# ADC.net
KiCad netlist of a schematic drawn in EAGLE
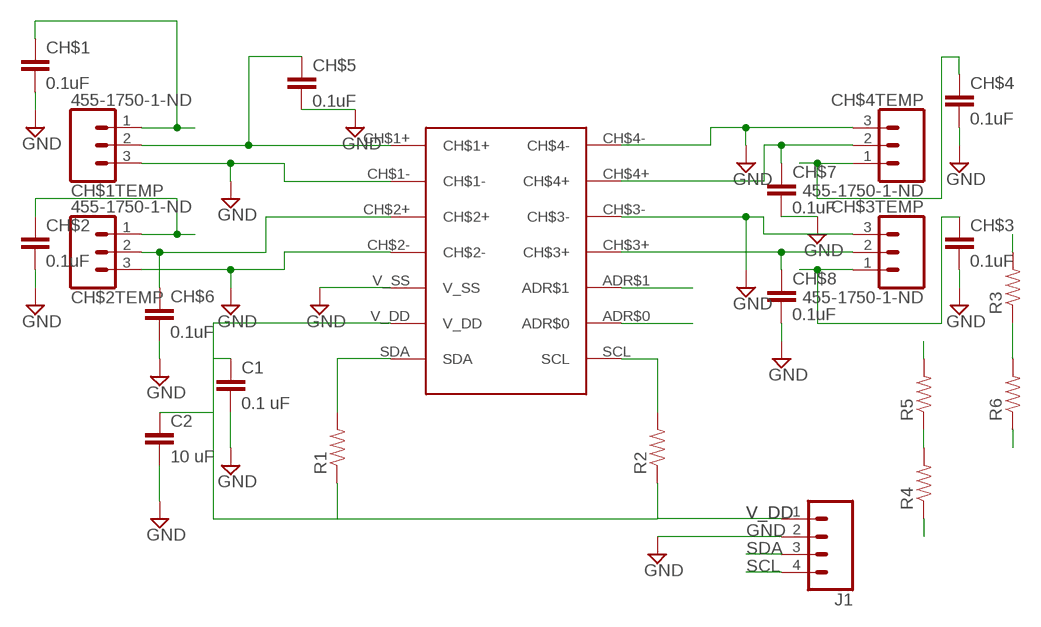
[diagram p0: schematic, sheet 1]

(export (version "E")
  (design (tool "Eeschema 10.0.6"))
  (components
    (comp (ref "C1")
      (value "0.1 uF")
      (footprint "eagle-import:0805")
      (libsource (lib "eagle-import") (part "CAPACITOR0805"))
    )
    (comp (ref "C2")
      (value "10 uF")
      (footprint "eagle-import:0805")
      (libsource (lib "eagle-import") (part "CAPACITOR0805"))
    )
    (comp (ref "CH$1")
      (value "0.1uF")
      (footprint "eagle-import:0805")
      (libsource (lib "eagle-import") (part "CAPACITOR0805"))
    )
    (comp (ref "CH$1TEMP")
      (value "455-1750-1-ND")
      (footprint "eagle-import:1X03")
      (libsource (lib "eagle-import") (part "CONN_03"))
    )
    (comp (ref "CH$2")
      (value "0.1uF")
      (footprint "eagle-import:0805")
      (libsource (lib "eagle-import") (part "CAPACITOR0805"))
    )
    (comp (ref "CH$2TEMP")
      (value "455-1750-1-ND")
      (footprint "eagle-import:1X03")
      (libsource (lib "eagle-import") (part "CONN_03"))
    )
    (comp (ref "CH$3")
      (value "0.1uF")
      (footprint "eagle-import:0805")
      (libsource (lib "eagle-import") (part "CAPACITOR0805"))
    )
    (comp (ref "CH$3TEMP")
      (value "455-1750-1-ND")
      (footprint "eagle-import:1X03")
      (libsource (lib "eagle-import") (part "CONN_03"))
    )
    (comp (ref "CH$4")
      (value "0.1uF")
      (footprint "eagle-import:0805")
      (libsource (lib "eagle-import") (part "CAPACITOR0805"))
    )
    (comp (ref "CH$4TEMP")
      (value "455-1750-1-ND")
      (footprint "eagle-import:1X03")
      (libsource (lib "eagle-import") (part "CONN_03"))
    )
    (comp (ref "CH$5")
      (value "0.1uF")
      (footprint "eagle-import:0805")
      (libsource (lib "eagle-import") (part "CAPACITOR0805"))
    )
    (comp (ref "CH$6")
      (value "0.1uF")
      (footprint "eagle-import:0805")
      (libsource (lib "eagle-import") (part "CAPACITOR0805"))
    )
    (comp (ref "CH$7")
      (value "0.1uF")
      (footprint "eagle-import:0805")
      (libsource (lib "eagle-import") (part "CAPACITOR0805"))
    )
    (comp (ref "CH$8")
      (value "0.1uF")
      (footprint "eagle-import:0805")
      (libsource (lib "eagle-import") (part "CAPACITOR0805"))
    )
    (comp (ref "J1")
      (value "CONN_04")
      (footprint "eagle-import:1X04")
      (libsource (lib "eagle-import") (part "CONN_04"))
    )
    (comp (ref "R1")
      (value "RESISTOR0805")
      (footprint "eagle-import:0805")
      (libsource (lib "eagle-import") (part "RESISTOR0805"))
    )
    (comp (ref "R2")
      (value "RESISTOR0805")
      (footprint "eagle-import:0805")
      (libsource (lib "eagle-import") (part "RESISTOR0805"))
    )
    (comp (ref "R3")
      (value "RESISTOR0805")
      (footprint "eagle-import:0805")
      (libsource (lib "eagle-import") (part "RESISTOR0805"))
    )
    (comp (ref "R4")
      (value "RESISTOR0805")
      (footprint "eagle-import:0805")
      (libsource (lib "eagle-import") (part "RESISTOR0805"))
    )
    (comp (ref "R5")
      (value "RESISTOR0805")
      (footprint "eagle-import:0805")
      (libsource (lib "eagle-import") (part "RESISTOR0805"))
    )
    (comp (ref "R6")
      (value "RESISTOR0805")
      (footprint "eagle-import:0805")
      (libsource (lib "eagle-import") (part "RESISTOR0805"))
    )
    (comp (ref "U$1")
      (value "MCP3428-E/SL")
      (footprint "eagle-import:MICROCHIP_MCP3428")
      (libsource (lib "eagle-import") (part "MCP3428-E/SL"))
    )
  )
  (nets
    (net (code "1") (name "/ADR0") (class "Default")
      (node (ref "R4") (pin "2") (pinfunction "2_2") (pintype "passive"))
      (node (ref "R5") (pin "1") (pinfunction "1_1") (pintype "passive"))
      (node (ref "U$1") (pin "ADR$0") (pinfunction "ADR$0_ADR$0") (pintype "bidirectional"))
    )
    (net (code "2") (name "/ADR1") (class "Default")
      (node (ref "R3") (pin "1") (pinfunction "1_1") (pintype "passive"))
      (node (ref "R6") (pin "2") (pinfunction "2_2") (pintype "passive"))
      (node (ref "U$1") (pin "ADR$1") (pinfunction "ADR$1_ADR$1") (pintype "bidirectional"))
    )
    (net (code "3") (name "/SCL") (class "Default")
      (node (ref "J1") (pin "4") (pinfunction "4_4") (pintype "passive"))
      (node (ref "R2") (pin "2") (pinfunction "2_2") (pintype "passive"))
      (node (ref "U$1") (pin "SCL") (pinfunction "SCL_SCL") (pintype "bidirectional"))
    )
    (net (code "4") (name "/SDA") (class "Default")
      (node (ref "J1") (pin "3") (pinfunction "3_3") (pintype "passive"))
      (node (ref "R1") (pin "2") (pinfunction "2_2") (pintype "passive"))
      (node (ref "U$1") (pin "SDA") (pinfunction "SDA_SDA") (pintype "bidirectional"))
    )
    (net (code "5") (name "/V_DD") (class "Default")
      (node (ref "C1") (pin "1") (pinfunction "1_1") (pintype "passive"))
      (node (ref "C2") (pin "1") (pinfunction "1_1") (pintype "passive"))
      (node (ref "CH$1") (pin "1") (pinfunction "1_1") (pintype "passive"))
      (node (ref "CH$1TEMP") (pin "1") (pinfunction "1_1") (pintype "passive"))
      (node (ref "CH$2") (pin "1") (pinfunction "1_1") (pintype "passive"))
      (node (ref "CH$2TEMP") (pin "1") (pinfunction "1_1") (pintype "passive"))
      (node (ref "CH$3") (pin "1") (pinfunction "1_1") (pintype "passive"))
      (node (ref "CH$3TEMP") (pin "1") (pinfunction "1_1") (pintype "passive"))
      (node (ref "CH$4") (pin "1") (pinfunction "1_1") (pintype "passive"))
      (node (ref "CH$4TEMP") (pin "1") (pinfunction "1_1") (pintype "passive"))
      (node (ref "J1") (pin "1") (pinfunction "1_1") (pintype "passive"))
      (node (ref "R1") (pin "1") (pinfunction "1_1") (pintype "passive"))
      (node (ref "R2") (pin "1") (pinfunction "1_1") (pintype "passive"))
      (node (ref "R3") (pin "2") (pinfunction "2_2") (pintype "passive"))
      (node (ref "R5") (pin "2") (pinfunction "2_2") (pintype "passive"))
      (node (ref "U$1") (pin "V_DD") (pinfunction "V_DD_V_DD") (pintype "bidirectional"))
    )
    (net (code "6") (name "GND") (class "Default")
      (node (ref "C1") (pin "2") (pinfunction "2_2") (pintype "passive"))
      (node (ref "C2") (pin "2") (pinfunction "2_2") (pintype "passive"))
      (node (ref "CH$1") (pin "2") (pinfunction "2_2") (pintype "passive"))
      (node (ref "CH$1TEMP") (pin "3") (pinfunction "3_3") (pintype "passive"))
      (node (ref "CH$2") (pin "2") (pinfunction "2_2") (pintype "passive"))
      (node (ref "CH$2TEMP") (pin "3") (pinfunction "3_3") (pintype "passive"))
      (node (ref "CH$3") (pin "2") (pinfunction "2_2") (pintype "passive"))
      (node (ref "CH$3TEMP") (pin "3") (pinfunction "3_3") (pintype "passive"))
      (node (ref "CH$4") (pin "2") (pinfunction "2_2") (pintype "passive"))
      (node (ref "CH$4TEMP") (pin "3") (pinfunction "3_3") (pintype "passive"))
      (node (ref "CH$5") (pin "2") (pinfunction "2_2") (pintype "passive"))
      (node (ref "CH$6") (pin "2") (pinfunction "2_2") (pintype "passive"))
      (node (ref "CH$7") (pin "2") (pinfunction "2_2") (pintype "passive"))
      (node (ref "CH$8") (pin "2") (pinfunction "2_2") (pintype "passive"))
      (node (ref "J1") (pin "2") (pinfunction "2_2") (pintype "passive"))
      (node (ref "R4") (pin "1") (pinfunction "1_1") (pintype "passive"))
      (node (ref "R6") (pin "1") (pinfunction "1_1") (pintype "passive"))
      (node (ref "U$1") (pin "CH$1-") (pinfunction "CH$1-_CH$1-") (pintype "bidirectional"))
      (node (ref "U$1") (pin "CH$2-") (pinfunction "CH$2-_CH$2-") (pintype "bidirectional"))
      (node (ref "U$1") (pin "CH$3-") (pinfunction "CH$3-_CH$3-") (pintype "bidirectional"))
      (node (ref "U$1") (pin "CH$4-") (pinfunction "CH$4-_CH$4-") (pintype "bidirectional"))
      (node (ref "U$1") (pin "V_SS") (pinfunction "V_SS_V_SS") (pintype "bidirectional"))
    )
    (net (code "7") (name "Net-(CH$1TEMP-Pad2)") (class "Default")
      (node (ref "CH$1TEMP") (pin "2") (pinfunction "2_2") (pintype "passive"))
      (node (ref "CH$5") (pin "1") (pinfunction "1_1") (pintype "passive"))
      (node (ref "U$1") (pin "CH$1+") (pinfunction "CH$1+_CH$1+") (pintype "bidirectional"))
    )
    (net (code "8") (name "Net-(CH$2TEMP-Pad2)") (class "Default")
      (node (ref "CH$2TEMP") (pin "2") (pinfunction "2_2") (pintype "passive"))
      (node (ref "CH$6") (pin "1") (pinfunction "1_1") (pintype "passive"))
      (node (ref "U$1") (pin "CH$2+") (pinfunction "CH$2+_CH$2+") (pintype "bidirectional"))
    )
    (net (code "9") (name "Net-(CH$3TEMP-Pad2)") (class "Default")
      (node (ref "CH$3TEMP") (pin "2") (pinfunction "2_2") (pintype "passive"))
      (node (ref "CH$8") (pin "1") (pinfunction "1_1") (pintype "passive"))
      (node (ref "U$1") (pin "CH$3+") (pinfunction "CH$3+_CH$3+") (pintype "bidirectional"))
    )
    (net (code "10") (name "Net-(CH$4TEMP-Pad2)") (class "Default")
      (node (ref "CH$4TEMP") (pin "2") (pinfunction "2_2") (pintype "passive"))
      (node (ref "CH$7") (pin "1") (pinfunction "1_1") (pintype "passive"))
      (node (ref "U$1") (pin "CH$4+") (pinfunction "CH$4+_CH$4+") (pintype "bidirectional"))
    )
  )
)
